# HyperRAM.net
KiCad netlist of a schematic drawn in Altium Designer
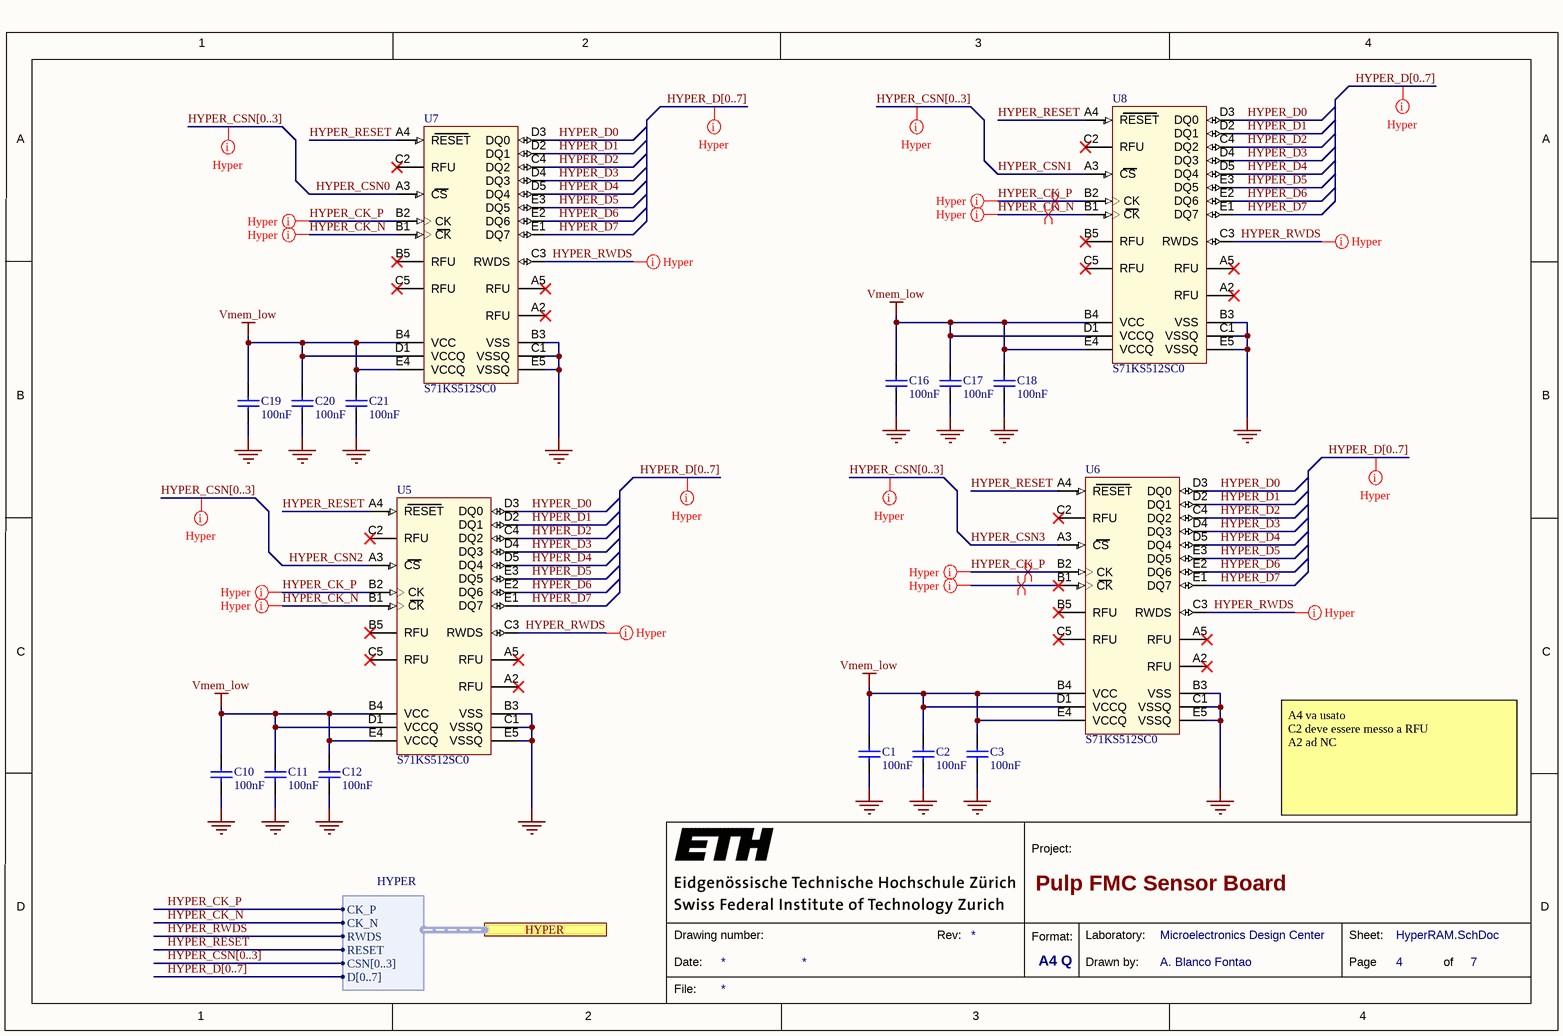
[diagram p0: HyperRAM.SchDoc]

(export (version "E")
  (design (tool "Eeschema 10.0.6"))
  (components
    (comp (ref "C1")
      (value "100nF")
      (footprint "CAPC0603(1608)100_N")
      (description "CAP 100nF 25V ±10% 0603 (1608 Metric) Thickness 1mm SMD")
      (fields (field (name "TOLERANCE") "Â±10%") (field (name "Comment") "CAP 100nF 25V 0603(1608)"))
      (libsource (lib "Altium Content Vault") (part "CMP-1035-02588-1"))
    )
    (comp (ref "C2")
      (value "100nF")
      (footprint "CAPC0603(1608)100_N")
      (description "CAP 100nF 25V ±10% 0603 (1608 Metric) Thickness 1mm SMD")
      (fields (field (name "TOLERANCE") "Â±10%") (field (name "Comment") "CAP 100nF 25V 0603(1608)"))
      (libsource (lib "Altium Content Vault") (part "CMP-1035-02588-1"))
    )
    (comp (ref "C3")
      (value "100nF")
      (footprint "CAPC0603(1608)100_N")
      (description "CAP 100nF 25V ±10% 0603 (1608 Metric) Thickness 1mm SMD")
      (fields (field (name "TOLERANCE") "Â±10%") (field (name "Comment") "CAP 100nF 25V 0603(1608)"))
      (libsource (lib "Altium Content Vault") (part "CMP-1035-02588-1"))
    )
    (comp (ref "C10")
      (value "100nF")
      (footprint "CAPC0603(1608)100_N")
      (description "CAP 100nF 25V ±10% 0603 (1608 Metric) Thickness 1mm SMD")
      (fields (field (name "TOLERANCE") "Â±10%") (field (name "Comment") "CAP 100nF 25V 0603(1608)"))
      (libsource (lib "Altium Content Vault") (part "CMP-1035-02588-1"))
    )
    (comp (ref "C11")
      (value "100nF")
      (footprint "CAPC0603(1608)100_N")
      (description "CAP 100nF 25V ±10% 0603 (1608 Metric) Thickness 1mm SMD")
      (fields (field (name "TOLERANCE") "Â±10%") (field (name "Comment") "CAP 100nF 25V 0603(1608)"))
      (libsource (lib "Altium Content Vault") (part "CMP-1035-02588-1"))
    )
    (comp (ref "C12")
      (value "100nF")
      (footprint "CAPC0603(1608)100_N")
      (description "CAP 100nF 25V ±10% 0603 (1608 Metric) Thickness 1mm SMD")
      (fields (field (name "TOLERANCE") "Â±10%") (field (name "Comment") "CAP 100nF 25V 0603(1608)"))
      (libsource (lib "Altium Content Vault") (part "CMP-1035-02588-1"))
    )
    (comp (ref "C16")
      (value "100nF")
      (footprint "CAPC0603(1608)100_N")
      (description "CAP 100nF 25V ±10% 0603 (1608 Metric) Thickness 1mm SMD")
      (fields (field (name "TOLERANCE") "Â±10%") (field (name "Comment") "CAP 100nF 25V 0603(1608)"))
      (libsource (lib "Altium Content Vault") (part "CMP-1035-02588-1"))
    )
    (comp (ref "C17")
      (value "100nF")
      (footprint "CAPC0603(1608)100_N")
      (description "CAP 100nF 25V ±10% 0603 (1608 Metric) Thickness 1mm SMD")
      (fields (field (name "TOLERANCE") "Â±10%") (field (name "Comment") "CAP 100nF 25V 0603(1608)"))
      (libsource (lib "Altium Content Vault") (part "CMP-1035-02588-1"))
    )
    (comp (ref "C18")
      (value "100nF")
      (footprint "CAPC0603(1608)100_N")
      (description "CAP 100nF 25V ±10% 0603 (1608 Metric) Thickness 1mm SMD")
      (fields (field (name "TOLERANCE") "Â±10%") (field (name "Comment") "CAP 100nF 25V 0603(1608)"))
      (libsource (lib "Altium Content Vault") (part "CMP-1035-02588-1"))
    )
    (comp (ref "C19")
      (value "100nF")
      (footprint "CAPC0603(1608)100_N")
      (description "CAP 100nF 25V ±10% 0603 (1608 Metric) Thickness 1mm SMD")
      (fields (field (name "TOLERANCE") "Â±10%") (field (name "Comment") "CAP 100nF 25V 0603(1608)"))
      (libsource (lib "Altium Content Vault") (part "CMP-1035-02588-1"))
    )
    (comp (ref "C20")
      (value "100nF")
      (footprint "CAPC0603(1608)100_N")
      (description "CAP 100nF 25V ±10% 0603 (1608 Metric) Thickness 1mm SMD")
      (fields (field (name "TOLERANCE") "Â±10%") (field (name "Comment") "CAP 100nF 25V 0603(1608)"))
      (libsource (lib "Altium Content Vault") (part "CMP-1035-02588-1"))
    )
    (comp (ref "C21")
      (value "100nF")
      (footprint "CAPC0603(1608)100_N")
      (description "CAP 100nF 25V ±10% 0603 (1608 Metric) Thickness 1mm SMD")
      (fields (field (name "TOLERANCE") "Â±10%") (field (name "Comment") "CAP 100nF 25V 0603(1608)"))
      (libsource (lib "Altium Content Vault") (part "CMP-1035-02588-1"))
    )
    (comp (ref "U5")
      (value "S71KS512SC0")
      (footprint "FBGA24_A-130")
      (description "Cypress 64Mbit DRAM 24FBGA HyperRam")
      (libsource (lib "hyperRAM") (part "S80KS5122"))
    )
    (comp (ref "U6")
      (value "S71KS512SC0")
      (footprint "FBGA24_A-130")
      (description "Cypress 64Mbit DRAM 24FBGA HyperRam")
      (libsource (lib "hyperRAM") (part "S80KS5122"))
    )
    (comp (ref "U7")
      (value "S71KS512SC0")
      (footprint "FBGA24_A-130")
      (description "Cypress 64Mbit DRAM 24FBGA HyperRam")
      (libsource (lib "hyperRAM") (part "S80KS5122"))
    )
    (comp (ref "U8")
      (value "S71KS512SC0")
      (footprint "FBGA24_A-130")
      (description "Cypress 64Mbit DRAM 24FBGA HyperRam")
      (libsource (lib "hyperRAM") (part "S80KS5122"))
    )
  )
  (nets
    (net (code "2") (name "/HYPER_CK_N") (class "Default")
      (node (ref "U5") (pin "B1") (pinfunction "CK_B1") (pintype "input"))
      (node (ref "U7") (pin "B1") (pinfunction "CK_B1") (pintype "input"))
      (node (ref "U8") (pin "B1") (pinfunction "CK_B1") (pintype "input"))
    )
    (net (code "3") (name "/HYPER_CK_P") (class "Default")
      (node (ref "U5") (pin "B2") (pinfunction "CK_B2") (pintype "input"))
      (node (ref "U6") (pin "B2") (pinfunction "CK_B2") (pintype "input"))
      (node (ref "U7") (pin "B2") (pinfunction "CK_B2") (pintype "input"))
      (node (ref "U8") (pin "B2") (pinfunction "CK_B2") (pintype "input"))
    )
    (net (code "4") (name "/HYPER_CSN0") (class "Default")
      (node (ref "U7") (pin "A3") (pinfunction "CS_A3") (pintype "input"))
    )
    (net (code "5") (name "/HYPER_CSN1") (class "Default")
      (node (ref "U8") (pin "A3") (pinfunction "CS_A3") (pintype "input"))
    )
    (net (code "6") (name "/HYPER_CSN2") (class "Default")
      (node (ref "U5") (pin "A3") (pinfunction "CS_A3") (pintype "input"))
    )
    (net (code "7") (name "/HYPER_CSN3") (class "Default")
      (node (ref "U6") (pin "A3") (pinfunction "CS_A3") (pintype "input"))
    )
    (net (code "9") (name "/HYPER_D0") (class "Default")
      (node (ref "U5") (pin "D3") (pinfunction "DQ0_D3") (pintype "bidirectional"))
      (node (ref "U6") (pin "D3") (pinfunction "DQ0_D3") (pintype "bidirectional"))
      (node (ref "U7") (pin "D3") (pinfunction "DQ0_D3") (pintype "bidirectional"))
      (node (ref "U8") (pin "D3") (pinfunction "DQ0_D3") (pintype "bidirectional"))
    )
    (net (code "10") (name "/HYPER_D1") (class "Default")
      (node (ref "U5") (pin "D2") (pinfunction "DQ1_D2") (pintype "bidirectional"))
      (node (ref "U6") (pin "D2") (pinfunction "DQ1_D2") (pintype "bidirectional"))
      (node (ref "U7") (pin "D2") (pinfunction "DQ1_D2") (pintype "bidirectional"))
      (node (ref "U8") (pin "D2") (pinfunction "DQ1_D2") (pintype "bidirectional"))
    )
    (net (code "11") (name "/HYPER_D2") (class "Default")
      (node (ref "U5") (pin "C4") (pinfunction "DQ2_C4") (pintype "bidirectional"))
      (node (ref "U6") (pin "C4") (pinfunction "DQ2_C4") (pintype "bidirectional"))
      (node (ref "U7") (pin "C4") (pinfunction "DQ2_C4") (pintype "bidirectional"))
      (node (ref "U8") (pin "C4") (pinfunction "DQ2_C4") (pintype "bidirectional"))
    )
    (net (code "12") (name "/HYPER_D3") (class "Default")
      (node (ref "U5") (pin "D4") (pinfunction "DQ3_D4") (pintype "bidirectional"))
      (node (ref "U6") (pin "D4") (pinfunction "DQ3_D4") (pintype "bidirectional"))
      (node (ref "U7") (pin "D4") (pinfunction "DQ3_D4") (pintype "bidirectional"))
      (node (ref "U8") (pin "D4") (pinfunction "DQ3_D4") (pintype "bidirectional"))
    )
    (net (code "13") (name "/HYPER_D4") (class "Default")
      (node (ref "U5") (pin "D5") (pinfunction "DQ4_D5") (pintype "bidirectional"))
      (node (ref "U6") (pin "D5") (pinfunction "DQ4_D5") (pintype "bidirectional"))
      (node (ref "U7") (pin "D5") (pinfunction "DQ4_D5") (pintype "bidirectional"))
      (node (ref "U8") (pin "D5") (pinfunction "DQ4_D5") (pintype "bidirectional"))
    )
    (net (code "14") (name "/HYPER_D5") (class "Default")
      (node (ref "U5") (pin "E3") (pinfunction "DQ5_E3") (pintype "bidirectional"))
      (node (ref "U6") (pin "E3") (pinfunction "DQ5_E3") (pintype "bidirectional"))
      (node (ref "U7") (pin "E3") (pinfunction "DQ5_E3") (pintype "bidirectional"))
      (node (ref "U8") (pin "E3") (pinfunction "DQ5_E3") (pintype "bidirectional"))
    )
    (net (code "15") (name "/HYPER_D6") (class "Default")
      (node (ref "U5") (pin "E2") (pinfunction "DQ6_E2") (pintype "bidirectional"))
      (node (ref "U6") (pin "E2") (pinfunction "DQ6_E2") (pintype "bidirectional"))
      (node (ref "U7") (pin "E2") (pinfunction "DQ6_E2") (pintype "bidirectional"))
      (node (ref "U8") (pin "E2") (pinfunction "DQ6_E2") (pintype "bidirectional"))
    )
    (net (code "16") (name "/HYPER_D7") (class "Default")
      (node (ref "U5") (pin "E1") (pinfunction "DQ7_E1") (pintype "bidirectional"))
      (node (ref "U6") (pin "E1") (pinfunction "DQ7_E1") (pintype "bidirectional"))
      (node (ref "U7") (pin "E1") (pinfunction "DQ7_E1") (pintype "bidirectional"))
      (node (ref "U8") (pin "E1") (pinfunction "DQ7_E1") (pintype "bidirectional"))
    )
    (net (code "18") (name "/HYPER_RESET") (class "Default")
      (node (ref "U5") (pin "A4") (pinfunction "RESET_A4") (pintype "input"))
      (node (ref "U6") (pin "A4") (pinfunction "RESET_A4") (pintype "input"))
      (node (ref "U7") (pin "A4") (pinfunction "RESET_A4") (pintype "input"))
      (node (ref "U8") (pin "A4") (pinfunction "RESET_A4") (pintype "input"))
    )
    (net (code "19") (name "/HYPER_RWDS") (class "Default")
      (node (ref "U5") (pin "C3") (pinfunction "RWDS_C3") (pintype "bidirectional"))
      (node (ref "U6") (pin "C3") (pinfunction "RWDS_C3") (pintype "bidirectional"))
      (node (ref "U7") (pin "C3") (pinfunction "RWDS_C3") (pintype "bidirectional"))
      (node (ref "U8") (pin "C3") (pinfunction "RWDS_C3") (pintype "bidirectional"))
    )
    (net (code "21") (name "GND") (class "Default")
      (node (ref "C1") (pin "1") (pinfunction "1_1") (pintype "passive"))
      (node (ref "C10") (pin "1") (pinfunction "1_1") (pintype "passive"))
      (node (ref "C11") (pin "1") (pinfunction "1_1") (pintype "passive"))
      (node (ref "C12") (pin "1") (pinfunction "1_1") (pintype "passive"))
      (node (ref "C16") (pin "1") (pinfunction "1_1") (pintype "passive"))
      (node (ref "C17") (pin "1") (pinfunction "1_1") (pintype "passive"))
      (node (ref "C18") (pin "1") (pinfunction "1_1") (pintype "passive"))
      (node (ref "C19") (pin "1") (pinfunction "1_1") (pintype "passive"))
      (node (ref "C2") (pin "1") (pinfunction "1_1") (pintype "passive"))
      (node (ref "C20") (pin "1") (pinfunction "1_1") (pintype "passive"))
      (node (ref "C21") (pin "1") (pinfunction "1_1") (pintype "passive"))
      (node (ref "C3") (pin "1") (pinfunction "1_1") (pintype "passive"))
      (node (ref "U5") (pin "B3") (pinfunction "VSS_B3") (pintype "passive"))
      (node (ref "U5") (pin "C1") (pinfunction "VSSQ_C1") (pintype "passive"))
      (node (ref "U5") (pin "E5") (pinfunction "VSSQ_E5") (pintype "passive"))
      (node (ref "U6") (pin "B3") (pinfunction "VSS_B3") (pintype "passive"))
      (node (ref "U6") (pin "C1") (pinfunction "VSSQ_C1") (pintype "passive"))
      (node (ref "U6") (pin "E5") (pinfunction "VSSQ_E5") (pintype "passive"))
      (node (ref "U7") (pin "B3") (pinfunction "VSS_B3") (pintype "passive"))
      (node (ref "U7") (pin "C1") (pinfunction "VSSQ_C1") (pintype "passive"))
      (node (ref "U7") (pin "E5") (pinfunction "VSSQ_E5") (pintype "passive"))
      (node (ref "U8") (pin "B3") (pinfunction "VSS_B3") (pintype "passive"))
      (node (ref "U8") (pin "C1") (pinfunction "VSSQ_C1") (pintype "passive"))
      (node (ref "U8") (pin "E5") (pinfunction "VSSQ_E5") (pintype "passive"))
    )
    (net (code "22") (name "Vmem_low") (class "Default")
      (node (ref "C1") (pin "2") (pinfunction "2_2") (pintype "passive"))
      (node (ref "C10") (pin "2") (pinfunction "2_2") (pintype "passive"))
      (node (ref "C11") (pin "2") (pinfunction "2_2") (pintype "passive"))
      (node (ref "C12") (pin "2") (pinfunction "2_2") (pintype "passive"))
      (node (ref "C16") (pin "2") (pinfunction "2_2") (pintype "passive"))
      (node (ref "C17") (pin "2") (pinfunction "2_2") (pintype "passive"))
      (node (ref "C18") (pin "2") (pinfunction "2_2") (pintype "passive"))
      (node (ref "C19") (pin "2") (pinfunction "2_2") (pintype "passive"))
      (node (ref "C2") (pin "2") (pinfunction "2_2") (pintype "passive"))
      (node (ref "C20") (pin "2") (pinfunction "2_2") (pintype "passive"))
      (node (ref "C21") (pin "2") (pinfunction "2_2") (pintype "passive"))
      (node (ref "C3") (pin "2") (pinfunction "2_2") (pintype "passive"))
      (node (ref "U5") (pin "B4") (pinfunction "VCC_B4") (pintype "passive"))
      (node (ref "U5") (pin "D1") (pinfunction "VCCQ_D1") (pintype "passive"))
      (node (ref "U5") (pin "E4") (pinfunction "VCCQ_E4") (pintype "passive"))
      (node (ref "U6") (pin "B4") (pinfunction "VCC_B4") (pintype "passive"))
      (node (ref "U6") (pin "D1") (pinfunction "VCCQ_D1") (pintype "passive"))
      (node (ref "U6") (pin "E4") (pinfunction "VCCQ_E4") (pintype "passive"))
      (node (ref "U7") (pin "B4") (pinfunction "VCC_B4") (pintype "passive"))
      (node (ref "U7") (pin "D1") (pinfunction "VCCQ_D1") (pintype "passive"))
      (node (ref "U7") (pin "E4") (pinfunction "VCCQ_E4") (pintype "passive"))
      (node (ref "U8") (pin "B4") (pinfunction "VCC_B4") (pintype "passive"))
      (node (ref "U8") (pin "D1") (pinfunction "VCCQ_D1") (pintype "passive"))
      (node (ref "U8") (pin "E4") (pinfunction "VCCQ_E4") (pintype "passive"))
    )
    (net (code "23") (name "unconnected-(U5-RFU-PadA2)") (class "Default")
      (node (ref "U5") (pin "A2") (pinfunction "RFU_A2") (pintype "passive+no_connect"))
    )
    (net (code "24") (name "unconnected-(U5-RFU-PadA5)") (class "Default")
      (node (ref "U5") (pin "A5") (pinfunction "RFU_A5") (pintype "passive+no_connect"))
    )
    (net (code "25") (name "unconnected-(U5-RFU-PadB5)") (class "Default")
      (node (ref "U5") (pin "B5") (pinfunction "RFU_B5") (pintype "passive+no_connect"))
    )
    (net (code "26") (name "unconnected-(U5-RFU-PadC2)") (class "Default")
      (node (ref "U5") (pin "C2") (pinfunction "RFU_C2") (pintype "passive+no_connect"))
    )
    (net (code "27") (name "unconnected-(U5-RFU-PadC5)") (class "Default")
      (node (ref "U5") (pin "C5") (pinfunction "RFU_C5") (pintype "passive+no_connect"))
    )
    (net (code "28") (name "unconnected-(U6-CK-PadB1)") (class "Default")
      (node (ref "U6") (pin "B1") (pinfunction "CK_B1") (pintype "input+no_connect"))
    )
    (net (code "29") (name "unconnected-(U6-RFU-PadA2)") (class "Default")
      (node (ref "U6") (pin "A2") (pinfunction "RFU_A2") (pintype "passive+no_connect"))
    )
    (net (code "30") (name "unconnected-(U6-RFU-PadA5)") (class "Default")
      (node (ref "U6") (pin "A5") (pinfunction "RFU_A5") (pintype "passive+no_connect"))
    )
    (net (code "31") (name "unconnected-(U6-RFU-PadB5)") (class "Default")
      (node (ref "U6") (pin "B5") (pinfunction "RFU_B5") (pintype "passive+no_connect"))
    )
    (net (code "32") (name "unconnected-(U6-RFU-PadC2)") (class "Default")
      (node (ref "U6") (pin "C2") (pinfunction "RFU_C2") (pintype "passive+no_connect"))
    )
    (net (code "33") (name "unconnected-(U6-RFU-PadC5)") (class "Default")
      (node (ref "U6") (pin "C5") (pinfunction "RFU_C5") (pintype "passive+no_connect"))
    )
    (net (code "34") (name "unconnected-(U7-RFU-PadA2)") (class "Default")
      (node (ref "U7") (pin "A2") (pinfunction "RFU_A2") (pintype "passive+no_connect"))
    )
    (net (code "35") (name "unconnected-(U7-RFU-PadA5)") (class "Default")
      (node (ref "U7") (pin "A5") (pinfunction "RFU_A5") (pintype "passive+no_connect"))
    )
    (net (code "36") (name "unconnected-(U7-RFU-PadB5)") (class "Default")
      (node (ref "U7") (pin "B5") (pinfunction "RFU_B5") (pintype "passive+no_connect"))
    )
    (net (code "37") (name "unconnected-(U7-RFU-PadC2)") (class "Default")
      (node (ref "U7") (pin "C2") (pinfunction "RFU_C2") (pintype "passive+no_connect"))
    )
    (net (code "38") (name "unconnected-(U7-RFU-PadC5)") (class "Default")
      (node (ref "U7") (pin "C5") (pinfunction "RFU_C5") (pintype "passive+no_connect"))
    )
    (net (code "39") (name "unconnected-(U8-RFU-PadA2)") (class "Default")
      (node (ref "U8") (pin "A2") (pinfunction "RFU_A2") (pintype "passive+no_connect"))
    )
    (net (code "40") (name "unconnected-(U8-RFU-PadA5)") (class "Default")
      (node (ref "U8") (pin "A5") (pinfunction "RFU_A5") (pintype "passive+no_connect"))
    )
    (net (code "41") (name "unconnected-(U8-RFU-PadB5)") (class "Default")
      (node (ref "U8") (pin "B5") (pinfunction "RFU_B5") (pintype "passive+no_connect"))
    )
    (net (code "42") (name "unconnected-(U8-RFU-PadC2)") (class "Default")
      (node (ref "U8") (pin "C2") (pinfunction "RFU_C2") (pintype "passive+no_connect"))
    )
    (net (code "43") (name "unconnected-(U8-RFU-PadC5)") (class "Default")
      (node (ref "U8") (pin "C5") (pinfunction "RFU_C5") (pintype "passive+no_connect"))
    )
  )
)
